# TinyCube11b_Lib.net
KiCad netlist of a schematic drawn in EAGLE
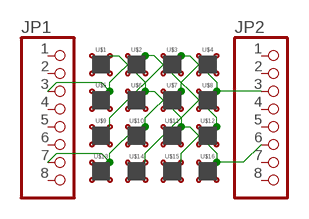
[diagram p0: schematic, sheet 1]

(export (version "E")
  (design (tool "Eeschema 10.0.6"))
  (components
    (comp (ref "JP1")
      (value "PINHD-1X8BIG")
      (footprint "eagle-import:1X08-BIG")
      (libsource (lib "eagle-import") (part "PINHD-1X8BIG"))
    )
    (comp (ref "JP2")
      (value "PINHD-1X8BIG")
      (footprint "eagle-import:1X08-BIG")
      (libsource (lib "eagle-import") (part "PINHD-1X8BIG"))
    )
    (comp (ref "U$1")
      (value "PILLAR")
      (footprint "eagle-import:10MIL")
      (libsource (lib "eagle-import") (part "PILLAR"))
    )
    (comp (ref "U$2")
      (value "PILLAR")
      (footprint "eagle-import:10MIL")
      (libsource (lib "eagle-import") (part "PILLAR"))
    )
    (comp (ref "U$3")
      (value "PILLAR")
      (footprint "eagle-import:10MIL")
      (libsource (lib "eagle-import") (part "PILLAR"))
    )
    (comp (ref "U$4")
      (value "PILLAR")
      (footprint "eagle-import:10MIL")
      (libsource (lib "eagle-import") (part "PILLAR"))
    )
    (comp (ref "U$5")
      (value "PILLAR")
      (footprint "eagle-import:10MIL")
      (libsource (lib "eagle-import") (part "PILLAR"))
    )
    (comp (ref "U$6")
      (value "PILLAR")
      (footprint "eagle-import:10MIL")
      (libsource (lib "eagle-import") (part "PILLAR"))
    )
    (comp (ref "U$7")
      (value "PILLAR")
      (footprint "eagle-import:10MIL")
      (libsource (lib "eagle-import") (part "PILLAR"))
    )
    (comp (ref "U$8")
      (value "PILLAR")
      (footprint "eagle-import:10MIL")
      (libsource (lib "eagle-import") (part "PILLAR"))
    )
    (comp (ref "U$9")
      (value "PILLAR")
      (footprint "eagle-import:10MIL")
      (libsource (lib "eagle-import") (part "PILLAR"))
    )
    (comp (ref "U$10")
      (value "PILLAR")
      (footprint "eagle-import:10MIL")
      (libsource (lib "eagle-import") (part "PILLAR"))
    )
    (comp (ref "U$11")
      (value "PILLAR")
      (footprint "eagle-import:10MIL")
      (libsource (lib "eagle-import") (part "PILLAR"))
    )
    (comp (ref "U$12")
      (value "PILLAR")
      (footprint "eagle-import:10MIL")
      (libsource (lib "eagle-import") (part "PILLAR"))
    )
    (comp (ref "U$13")
      (value "PILLAR")
      (footprint "eagle-import:10MIL")
      (libsource (lib "eagle-import") (part "PILLAR"))
    )
    (comp (ref "U$14")
      (value "PILLAR")
      (footprint "eagle-import:10MIL")
      (libsource (lib "eagle-import") (part "PILLAR"))
    )
    (comp (ref "U$15")
      (value "PILLAR")
      (footprint "eagle-import:10MIL")
      (libsource (lib "eagle-import") (part "PILLAR"))
    )
    (comp (ref "U$16")
      (value "PILLAR")
      (footprint "eagle-import:10MIL")
      (libsource (lib "eagle-import") (part "PILLAR"))
    )
  )
  (nets
    (net (code "1") (name "Net-(U$1-G)") (class "Default")
      (node (ref "JP2") (pin "6") (pinfunction "6_6") (pintype "passive"))
      (node (ref "U$1") (pin "+") (pinfunction "G_+") (pintype "bidirectional"))
      (node (ref "U$11") (pin "+") (pinfunction "G_+") (pintype "bidirectional"))
      (node (ref "U$16") (pin "+") (pinfunction "G_+") (pintype "bidirectional"))
      (node (ref "U$6") (pin "+") (pinfunction "G_+") (pintype "bidirectional"))
    )
    (net (code "2") (name "Net-(U$10-G)") (class "Default")
      (node (ref "JP1") (pin "7") (pinfunction "7_7") (pintype "passive"))
      (node (ref "U$10") (pin "+") (pinfunction "G_+") (pintype "bidirectional"))
      (node (ref "U$13") (pin "+") (pinfunction "G_+") (pintype "bidirectional"))
      (node (ref "U$4") (pin "+") (pinfunction "G_+") (pintype "bidirectional"))
      (node (ref "U$7") (pin "+") (pinfunction "G_+") (pintype "bidirectional"))
    )
    (net (code "3") (name "Net-(U$12-G)") (class "Default")
      (node (ref "JP1") (pin "3") (pinfunction "3_3") (pintype "passive"))
      (node (ref "U$12") (pin "+") (pinfunction "G_+") (pintype "bidirectional"))
      (node (ref "U$15") (pin "+") (pinfunction "G_+") (pintype "bidirectional"))
      (node (ref "U$2") (pin "+") (pinfunction "G_+") (pintype "bidirectional"))
      (node (ref "U$5") (pin "+") (pinfunction "G_+") (pintype "bidirectional"))
    )
    (net (code "4") (name "Net-(U$14-G)") (class "Default")
      (node (ref "JP2") (pin "3") (pinfunction "3_3") (pintype "passive"))
      (node (ref "U$14") (pin "+") (pinfunction "G_+") (pintype "bidirectional"))
      (node (ref "U$3") (pin "+") (pinfunction "G_+") (pintype "bidirectional"))
      (node (ref "U$8") (pin "+") (pinfunction "G_+") (pintype "bidirectional"))
      (node (ref "U$9") (pin "+") (pinfunction "G_+") (pintype "bidirectional"))
    )
    (net (code "5") (name "unconnected-(JP1-Pad1)") (class "Default")
      (node (ref "JP1") (pin "1") (pinfunction "1_1") (pintype "passive"))
    )
    (net (code "6") (name "unconnected-(JP1-Pad2)") (class "Default")
      (node (ref "JP1") (pin "2") (pinfunction "2_2") (pintype "passive"))
    )
    (net (code "7") (name "unconnected-(JP1-Pad4)") (class "Default")
      (node (ref "JP1") (pin "4") (pinfunction "4_4") (pintype "passive"))
    )
    (net (code "8") (name "unconnected-(JP1-Pad5)") (class "Default")
      (node (ref "JP1") (pin "5") (pinfunction "5_5") (pintype "passive"))
    )
    (net (code "9") (name "unconnected-(JP1-Pad6)") (class "Default")
      (node (ref "JP1") (pin "6") (pinfunction "6_6") (pintype "passive"))
    )
    (net (code "10") (name "unconnected-(JP1-Pad8)") (class "Default")
      (node (ref "JP1") (pin "8") (pinfunction "8_8") (pintype "passive"))
    )
    (net (code "11") (name "unconnected-(JP2-Pad1)") (class "Default")
      (node (ref "JP2") (pin "1") (pinfunction "1_1") (pintype "passive"))
    )
    (net (code "12") (name "unconnected-(JP2-Pad2)") (class "Default")
      (node (ref "JP2") (pin "2") (pinfunction "2_2") (pintype "passive"))
    )
    (net (code "13") (name "unconnected-(JP2-Pad4)") (class "Default")
      (node (ref "JP2") (pin "4") (pinfunction "4_4") (pintype "passive"))
    )
    (net (code "14") (name "unconnected-(JP2-Pad5)") (class "Default")
      (node (ref "JP2") (pin "5") (pinfunction "5_5") (pintype "passive"))
    )
    (net (code "15") (name "unconnected-(JP2-Pad7)") (class "Default")
      (node (ref "JP2") (pin "7") (pinfunction "7_7") (pintype "passive"))
    )
    (net (code "16") (name "unconnected-(JP2-Pad8)") (class "Default")
      (node (ref "JP2") (pin "8") (pinfunction "8_8") (pintype "passive"))
    )
    (net (code "17") (name "unconnected-(U$1-A-PadG)") (class "Default")
      (node (ref "U$1") (pin "G") (pinfunction "A_G") (pintype "bidirectional"))
    )
    (net (code "18") (name "unconnected-(U$1-B-PadR)") (class "Default")
      (node (ref "U$1") (pin "R") (pinfunction "B_R") (pintype "bidirectional"))
    )
    (net (code "19") (name "unconnected-(U$1-R-PadB)") (class "Default")
      (node (ref "U$1") (pin "B") (pinfunction "R_B") (pintype "bidirectional"))
    )
    (net (code "20") (name "unconnected-(U$2-A-PadG)") (class "Default")
      (node (ref "U$2") (pin "G") (pinfunction "A_G") (pintype "bidirectional"))
    )
    (net (code "21") (name "unconnected-(U$2-B-PadR)") (class "Default")
      (node (ref "U$2") (pin "R") (pinfunction "B_R") (pintype "bidirectional"))
    )
    (net (code "22") (name "unconnected-(U$2-R-PadB)") (class "Default")
      (node (ref "U$2") (pin "B") (pinfunction "R_B") (pintype "bidirectional"))
    )
    (net (code "23") (name "unconnected-(U$3-A-PadG)") (class "Default")
      (node (ref "U$3") (pin "G") (pinfunction "A_G") (pintype "bidirectional"))
    )
    (net (code "24") (name "unconnected-(U$3-B-PadR)") (class "Default")
      (node (ref "U$3") (pin "R") (pinfunction "B_R") (pintype "bidirectional"))
    )
    (net (code "25") (name "unconnected-(U$3-R-PadB)") (class "Default")
      (node (ref "U$3") (pin "B") (pinfunction "R_B") (pintype "bidirectional"))
    )
    (net (code "26") (name "unconnected-(U$4-A-PadG)") (class "Default")
      (node (ref "U$4") (pin "G") (pinfunction "A_G") (pintype "bidirectional"))
    )
    (net (code "27") (name "unconnected-(U$4-B-PadR)") (class "Default")
      (node (ref "U$4") (pin "R") (pinfunction "B_R") (pintype "bidirectional"))
    )
    (net (code "28") (name "unconnected-(U$4-R-PadB)") (class "Default")
      (node (ref "U$4") (pin "B") (pinfunction "R_B") (pintype "bidirectional"))
    )
    (net (code "29") (name "unconnected-(U$5-A-PadG)") (class "Default")
      (node (ref "U$5") (pin "G") (pinfunction "A_G") (pintype "bidirectional"))
    )
    (net (code "30") (name "unconnected-(U$5-B-PadR)") (class "Default")
      (node (ref "U$5") (pin "R") (pinfunction "B_R") (pintype "bidirectional"))
    )
    (net (code "31") (name "unconnected-(U$5-R-PadB)") (class "Default")
      (node (ref "U$5") (pin "B") (pinfunction "R_B") (pintype "bidirectional"))
    )
    (net (code "32") (name "unconnected-(U$6-A-PadG)") (class "Default")
      (node (ref "U$6") (pin "G") (pinfunction "A_G") (pintype "bidirectional"))
    )
    (net (code "33") (name "unconnected-(U$6-B-PadR)") (class "Default")
      (node (ref "U$6") (pin "R") (pinfunction "B_R") (pintype "bidirectional"))
    )
    (net (code "34") (name "unconnected-(U$6-R-PadB)") (class "Default")
      (node (ref "U$6") (pin "B") (pinfunction "R_B") (pintype "bidirectional"))
    )
    (net (code "35") (name "unconnected-(U$7-A-PadG)") (class "Default")
      (node (ref "U$7") (pin "G") (pinfunction "A_G") (pintype "bidirectional"))
    )
    (net (code "36") (name "unconnected-(U$7-B-PadR)") (class "Default")
      (node (ref "U$7") (pin "R") (pinfunction "B_R") (pintype "bidirectional"))
    )
    (net (code "37") (name "unconnected-(U$7-R-PadB)") (class "Default")
      (node (ref "U$7") (pin "B") (pinfunction "R_B") (pintype "bidirectional"))
    )
    (net (code "38") (name "unconnected-(U$8-A-PadG)") (class "Default")
      (node (ref "U$8") (pin "G") (pinfunction "A_G") (pintype "bidirectional"))
    )
    (net (code "39") (name "unconnected-(U$8-B-PadR)") (class "Default")
      (node (ref "U$8") (pin "R") (pinfunction "B_R") (pintype "bidirectional"))
    )
    (net (code "40") (name "unconnected-(U$8-R-PadB)") (class "Default")
      (node (ref "U$8") (pin "B") (pinfunction "R_B") (pintype "bidirectional"))
    )
    (net (code "41") (name "unconnected-(U$9-A-PadG)") (class "Default")
      (node (ref "U$9") (pin "G") (pinfunction "A_G") (pintype "bidirectional"))
    )
    (net (code "42") (name "unconnected-(U$9-B-PadR)") (class "Default")
      (node (ref "U$9") (pin "R") (pinfunction "B_R") (pintype "bidirectional"))
    )
    (net (code "43") (name "unconnected-(U$9-R-PadB)") (class "Default")
      (node (ref "U$9") (pin "B") (pinfunction "R_B") (pintype "bidirectional"))
    )
    (net (code "44") (name "unconnected-(U$10-A-PadG)") (class "Default")
      (node (ref "U$10") (pin "G") (pinfunction "A_G") (pintype "bidirectional"))
    )
    (net (code "45") (name "unconnected-(U$10-B-PadR)") (class "Default")
      (node (ref "U$10") (pin "R") (pinfunction "B_R") (pintype "bidirectional"))
    )
    (net (code "46") (name "unconnected-(U$10-R-PadB)") (class "Default")
      (node (ref "U$10") (pin "B") (pinfunction "R_B") (pintype "bidirectional"))
    )
    (net (code "47") (name "unconnected-(U$11-A-PadG)") (class "Default")
      (node (ref "U$11") (pin "G") (pinfunction "A_G") (pintype "bidirectional"))
    )
    (net (code "48") (name "unconnected-(U$11-B-PadR)") (class "Default")
      (node (ref "U$11") (pin "R") (pinfunction "B_R") (pintype "bidirectional"))
    )
    (net (code "49") (name "unconnected-(U$11-R-PadB)") (class "Default")
      (node (ref "U$11") (pin "B") (pinfunction "R_B") (pintype "bidirectional"))
    )
    (net (code "50") (name "unconnected-(U$12-A-PadG)") (class "Default")
      (node (ref "U$12") (pin "G") (pinfunction "A_G") (pintype "bidirectional"))
    )
    (net (code "51") (name "unconnected-(U$12-B-PadR)") (class "Default")
      (node (ref "U$12") (pin "R") (pinfunction "B_R") (pintype "bidirectional"))
    )
    (net (code "52") (name "unconnected-(U$12-R-PadB)") (class "Default")
      (node (ref "U$12") (pin "B") (pinfunction "R_B") (pintype "bidirectional"))
    )
    (net (code "53") (name "unconnected-(U$13-A-PadG)") (class "Default")
      (node (ref "U$13") (pin "G") (pinfunction "A_G") (pintype "bidirectional"))
    )
    (net (code "54") (name "unconnected-(U$13-B-PadR)") (class "Default")
      (node (ref "U$13") (pin "R") (pinfunction "B_R") (pintype "bidirectional"))
    )
    (net (code "55") (name "unconnected-(U$13-R-PadB)") (class "Default")
      (node (ref "U$13") (pin "B") (pinfunction "R_B") (pintype "bidirectional"))
    )
    (net (code "56") (name "unconnected-(U$14-A-PadG)") (class "Default")
      (node (ref "U$14") (pin "G") (pinfunction "A_G") (pintype "bidirectional"))
    )
    (net (code "57") (name "unconnected-(U$14-B-PadR)") (class "Default")
      (node (ref "U$14") (pin "R") (pinfunction "B_R") (pintype "bidirectional"))
    )
    (net (code "58") (name "unconnected-(U$14-R-PadB)") (class "Default")
      (node (ref "U$14") (pin "B") (pinfunction "R_B") (pintype "bidirectional"))
    )
    (net (code "59") (name "unconnected-(U$15-A-PadG)") (class "Default")
      (node (ref "U$15") (pin "G") (pinfunction "A_G") (pintype "bidirectional"))
    )
    (net (code "60") (name "unconnected-(U$15-B-PadR)") (class "Default")
      (node (ref "U$15") (pin "R") (pinfunction "B_R") (pintype "bidirectional"))
    )
    (net (code "61") (name "unconnected-(U$15-R-PadB)") (class "Default")
      (node (ref "U$15") (pin "B") (pinfunction "R_B") (pintype "bidirectional"))
    )
    (net (code "62") (name "unconnected-(U$16-A-PadG)") (class "Default")
      (node (ref "U$16") (pin "G") (pinfunction "A_G") (pintype "bidirectional"))
    )
    (net (code "63") (name "unconnected-(U$16-B-PadR)") (class "Default")
      (node (ref "U$16") (pin "R") (pinfunction "B_R") (pintype "bidirectional"))
    )
    (net (code "64") (name "unconnected-(U$16-R-PadB)") (class "Default")
      (node (ref "U$16") (pin "B") (pinfunction "R_B") (pintype "bidirectional"))
    )
  )
)
